# senseBox-MCU_mini_v11.net
KiCad netlist of a schematic drawn in EAGLE
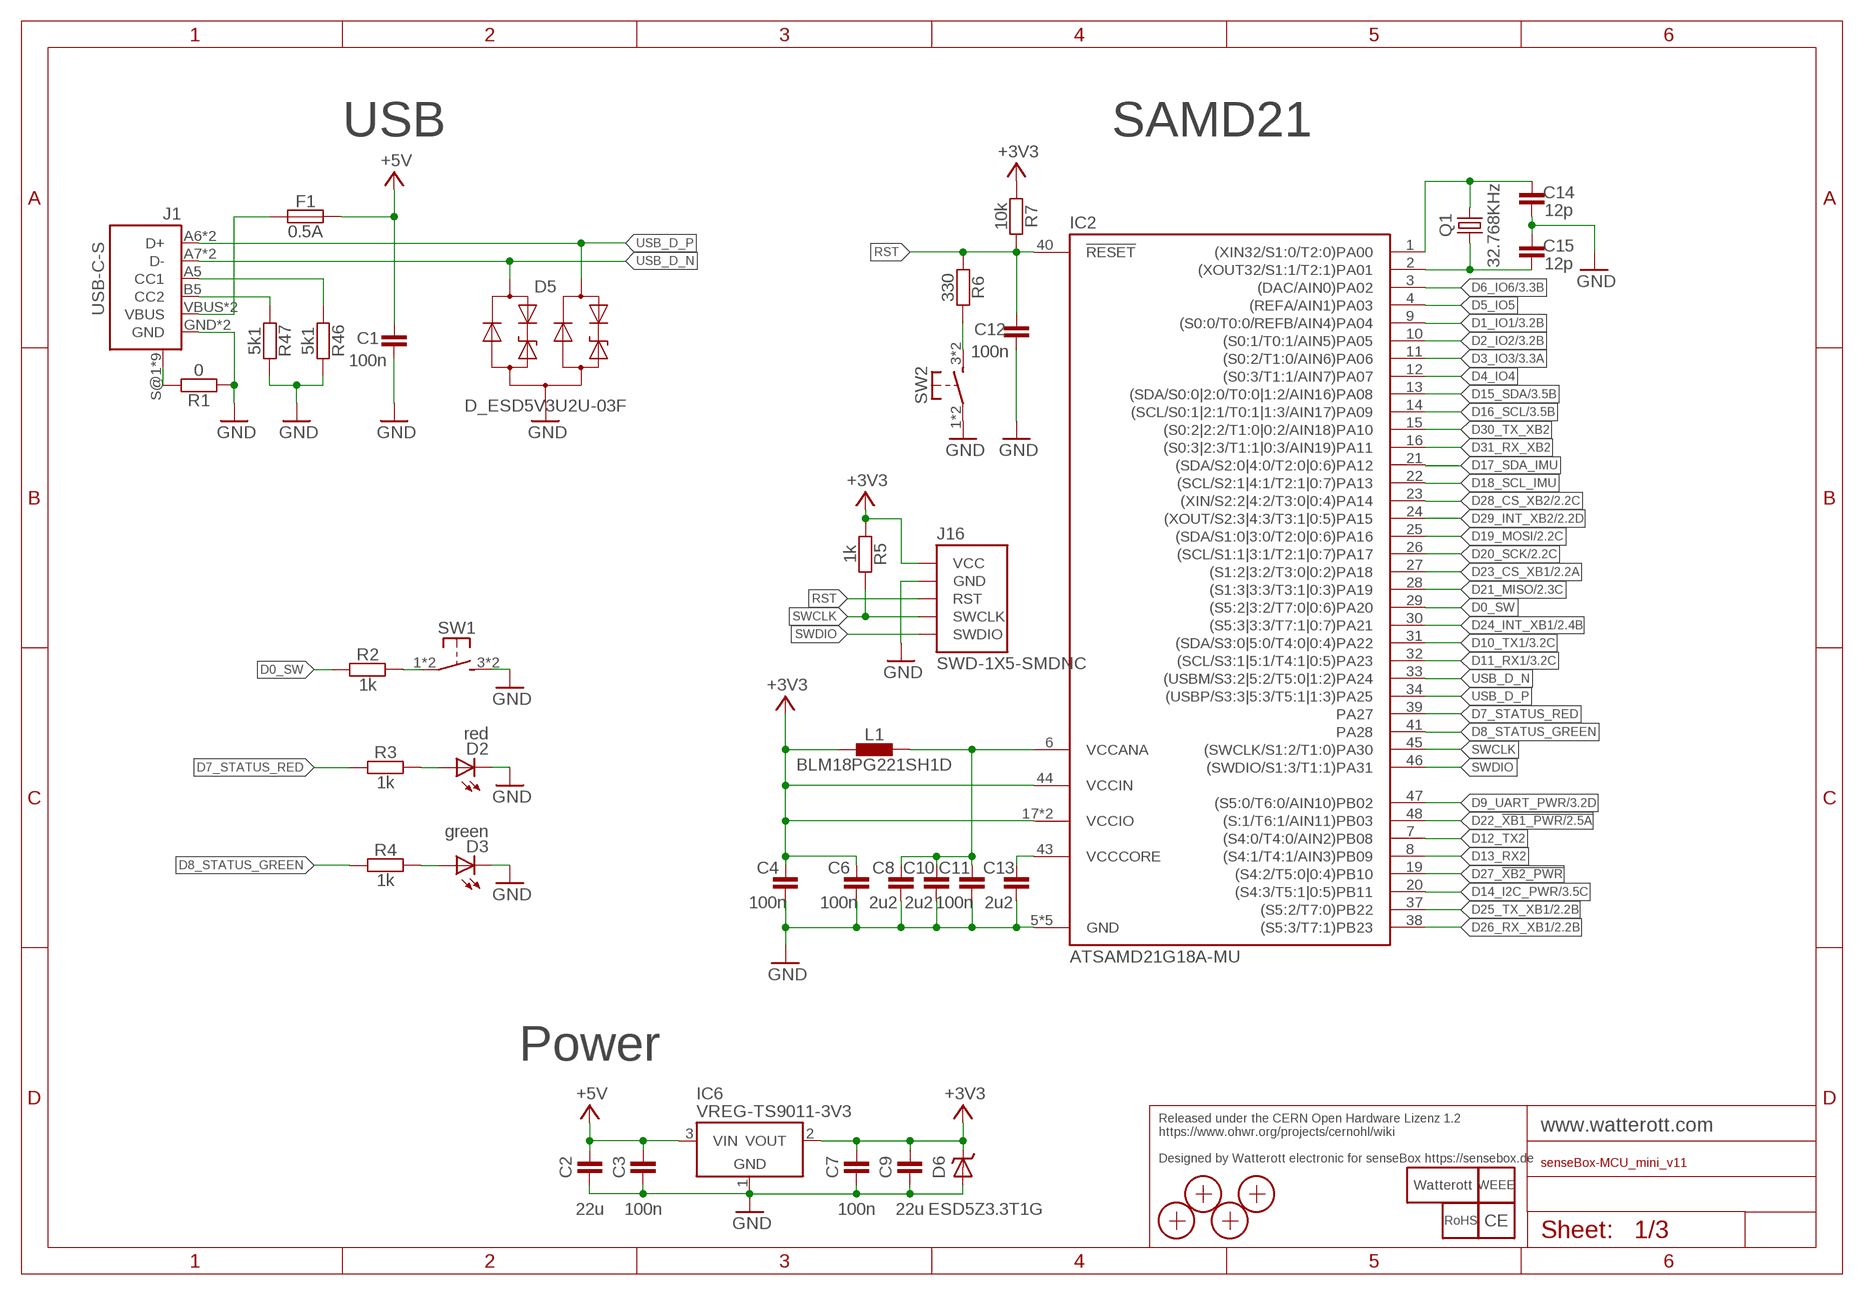
[diagram p0: schematic, sheet 1]
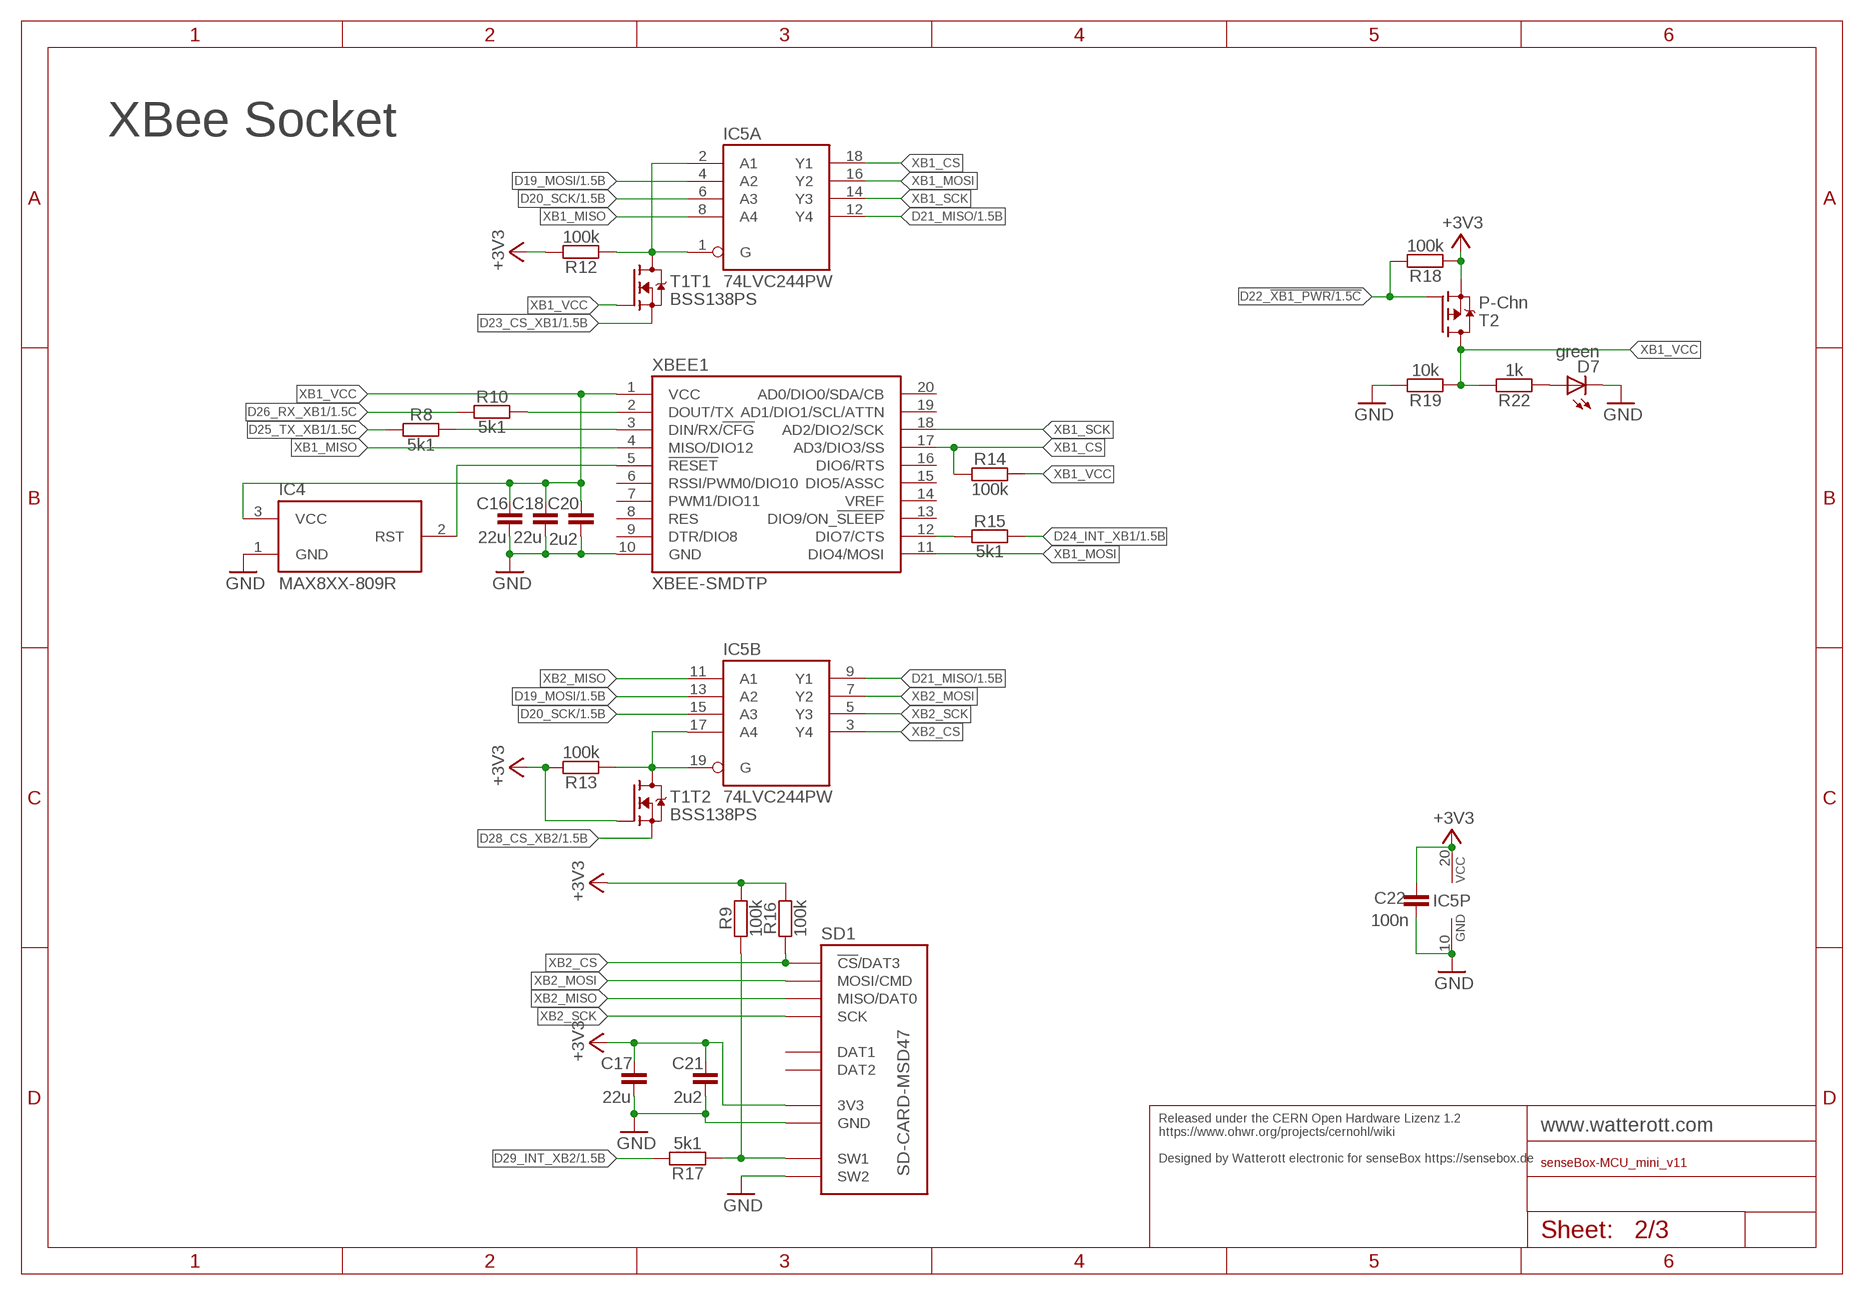
[diagram p1: schematic, sheet 2]
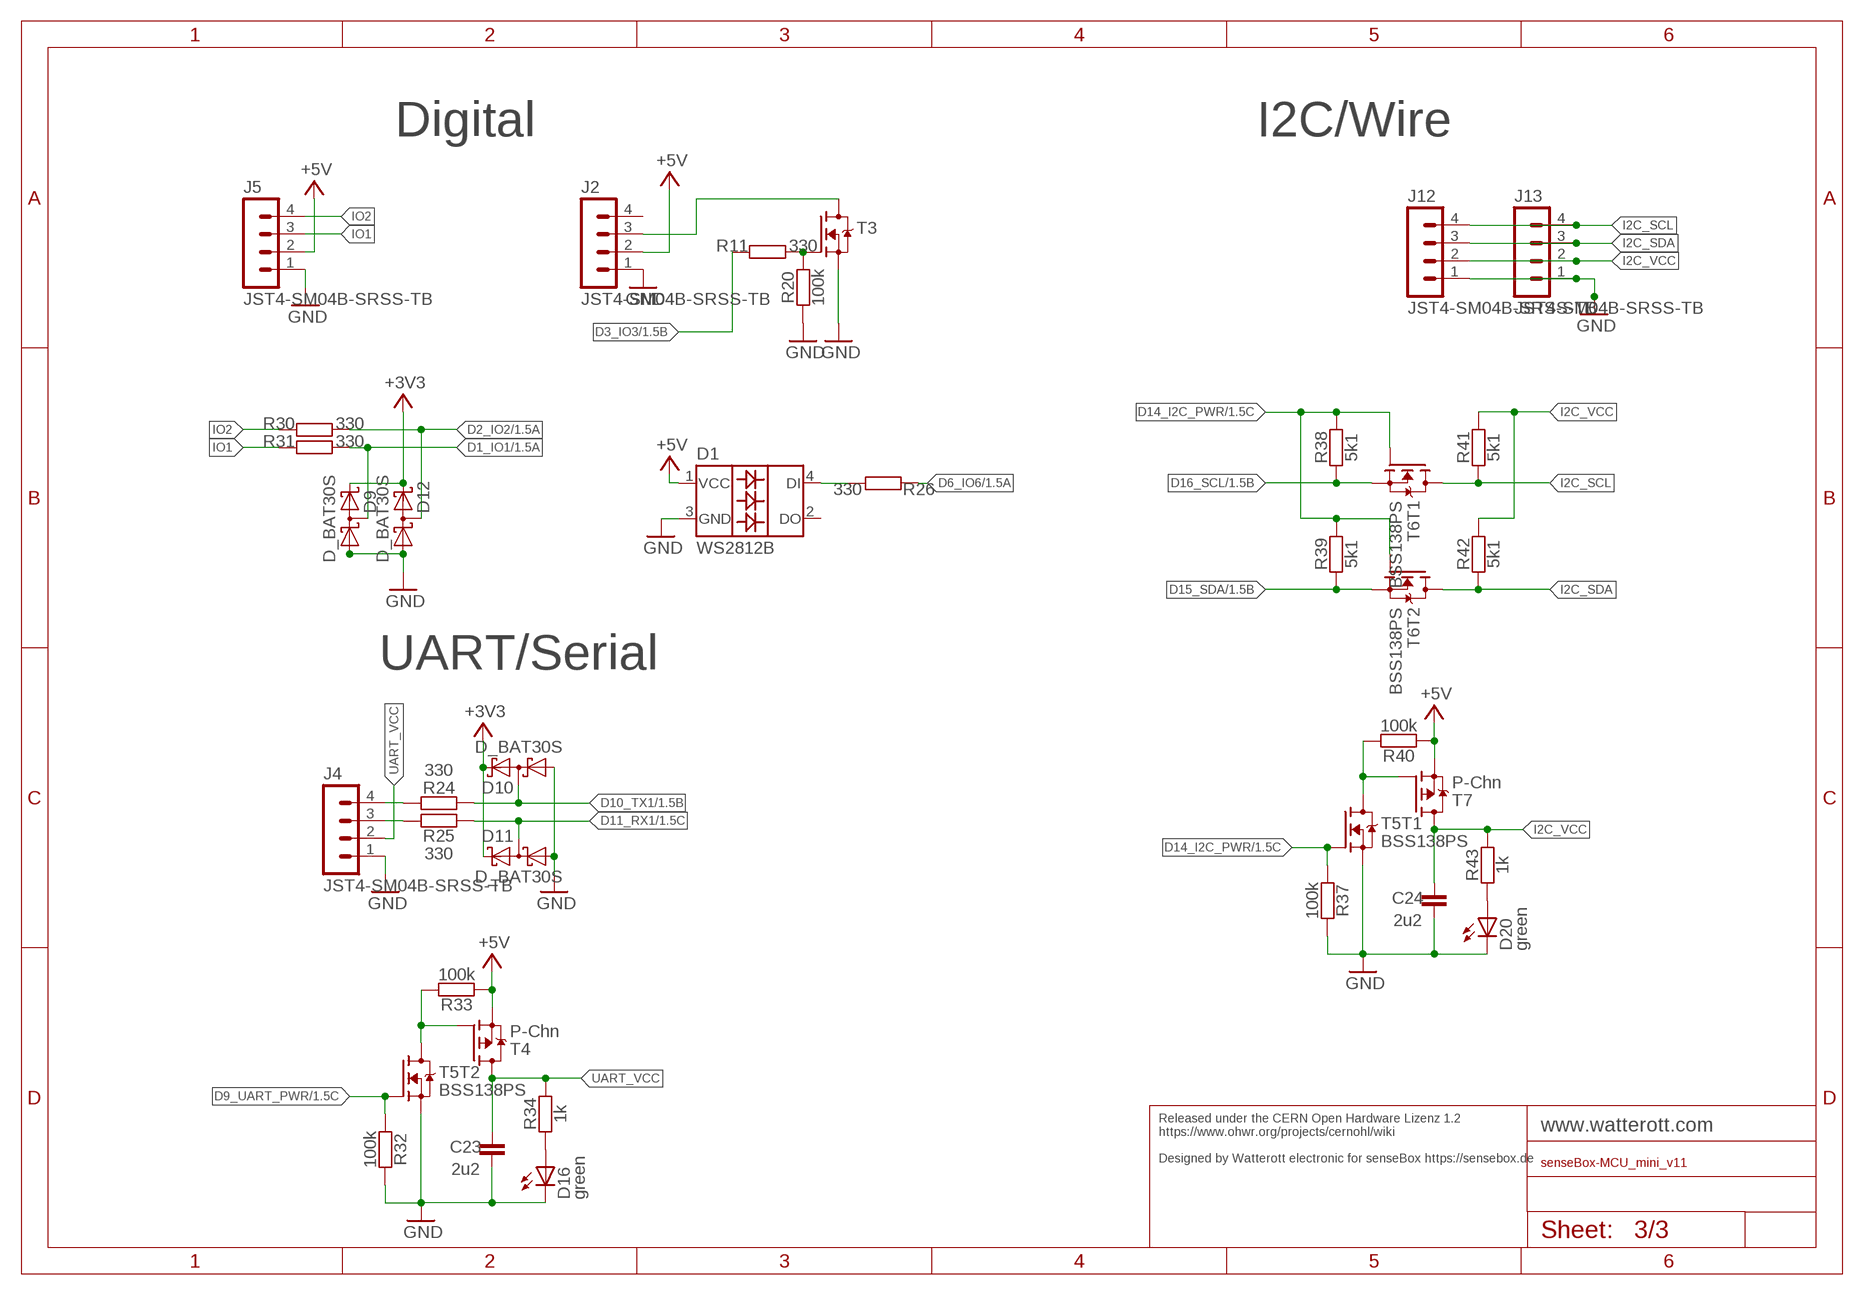
[diagram p2: schematic, sheet 3]

(export (version "E")
  (design (tool "Eeschema 10.0.6"))
  (components
    (comp (ref "C23")
      (value "2u2")
      (footprint "eagle-import:C0402")
      (libsource (lib "eagle-import") (part "CAPACITOR-0402"))
    )
    (comp (ref "C24")
      (value "2u2")
      (footprint "eagle-import:C0402")
      (libsource (lib "eagle-import") (part "CAPACITOR-0402"))
    )
    (comp (ref "D1")
      (value "WS2812B")
      (footprint "eagle-import:WS2812B")
      (libsource (lib "eagle-import") (part "WS2812B"))
    )
    (comp (ref "D9")
      (value "D_BAT30S")
      (footprint "eagle-import:SOT323")
      (libsource (lib "eagle-import") (part "D_BAT30S"))
    )
    (comp (ref "D10")
      (value "D_BAT30S")
      (footprint "eagle-import:SOT323")
      (libsource (lib "eagle-import") (part "D_BAT30S"))
    )
    (comp (ref "D11")
      (value "D_BAT30S")
      (footprint "eagle-import:SOT323")
      (libsource (lib "eagle-import") (part "D_BAT30S"))
    )
    (comp (ref "D12")
      (value "D_BAT30S")
      (footprint "eagle-import:SOT323")
      (libsource (lib "eagle-import") (part "D_BAT30S"))
    )
    (comp (ref "D16")
      (value "green")
      (footprint "eagle-import:C0603")
      (libsource (lib "eagle-import") (part "LED-0603"))
    )
    (comp (ref "D20")
      (value "green")
      (footprint "eagle-import:C0603")
      (libsource (lib "eagle-import") (part "LED-0603"))
    )
    (comp (ref "J2")
      (value "JST4-SM04B-SRSS-TB")
      (footprint "eagle-import:JST_SM04B-SRSS-TB")
      (libsource (lib "eagle-import") (part "JST4-SM04B-SRSS-TB"))
    )
    (comp (ref "J4")
      (value "JST4-SM04B-SRSS-TB")
      (footprint "eagle-import:JST_SM04B-SRSS-TB")
      (libsource (lib "eagle-import") (part "JST4-SM04B-SRSS-TB"))
    )
    (comp (ref "J5")
      (value "JST4-SM04B-SRSS-TB")
      (footprint "eagle-import:JST_SM04B-SRSS-TB")
      (libsource (lib "eagle-import") (part "JST4-SM04B-SRSS-TB"))
    )
    (comp (ref "J12")
      (value "JST4-SM04B-SRSS-TB")
      (footprint "eagle-import:JST_SM04B-SRSS-TB")
      (libsource (lib "eagle-import") (part "JST4-SM04B-SRSS-TB"))
    )
    (comp (ref "J13")
      (value "JST4-SM04B-SRSS-TB")
      (footprint "eagle-import:JST_SM04B-SRSS-TB")
      (libsource (lib "eagle-import") (part "JST4-SM04B-SRSS-TB"))
    )
    (comp (ref "R11")
      (value "330")
      (footprint "eagle-import:C0402")
      (libsource (lib "eagle-import") (part "RESISTOR-0402"))
    )
    (comp (ref "R20")
      (value "100k")
      (footprint "eagle-import:C0402")
      (libsource (lib "eagle-import") (part "RESISTOR-0402"))
    )
    (comp (ref "R24")
      (value "330")
      (footprint "eagle-import:C0402")
      (libsource (lib "eagle-import") (part "RESISTOR-0402"))
    )
    (comp (ref "R25")
      (value "330")
      (footprint "eagle-import:C0402")
      (libsource (lib "eagle-import") (part "RESISTOR-0402"))
    )
    (comp (ref "R26")
      (value "330")
      (footprint "eagle-import:C0402")
      (libsource (lib "eagle-import") (part "RESISTOR-0402"))
    )
    (comp (ref "R30")
      (value "330")
      (footprint "eagle-import:C0402")
      (libsource (lib "eagle-import") (part "RESISTOR-0402"))
    )
    (comp (ref "R31")
      (value "330")
      (footprint "eagle-import:C0402")
      (libsource (lib "eagle-import") (part "RESISTOR-0402"))
    )
    (comp (ref "R32")
      (value "100k")
      (footprint "eagle-import:C0402")
      (libsource (lib "eagle-import") (part "RESISTOR-0402"))
    )
    (comp (ref "R33")
      (value "100k")
      (footprint "eagle-import:C0402")
      (libsource (lib "eagle-import") (part "RESISTOR-0402"))
    )
    (comp (ref "R34")
      (value "1k")
      (footprint "eagle-import:C0402")
      (libsource (lib "eagle-import") (part "RESISTOR-0402"))
    )
    (comp (ref "R37")
      (value "100k")
      (footprint "eagle-import:C0402")
      (libsource (lib "eagle-import") (part "RESISTOR-0402"))
    )
    (comp (ref "R38")
      (value "5k1")
      (footprint "eagle-import:C0402")
      (libsource (lib "eagle-import") (part "RESISTOR-0402"))
    )
    (comp (ref "R39")
      (value "5k1")
      (footprint "eagle-import:C0402")
      (libsource (lib "eagle-import") (part "RESISTOR-0402"))
    )
    (comp (ref "R40")
      (value "100k")
      (footprint "eagle-import:C0402")
      (libsource (lib "eagle-import") (part "RESISTOR-0402"))
    )
    (comp (ref "R41")
      (value "5k1")
      (footprint "eagle-import:C0402")
      (libsource (lib "eagle-import") (part "RESISTOR-0402"))
    )
    (comp (ref "R42")
      (value "5k1")
      (footprint "eagle-import:C0402")
      (libsource (lib "eagle-import") (part "RESISTOR-0402"))
    )
    (comp (ref "R43")
      (value "1k")
      (footprint "eagle-import:C0402")
      (libsource (lib "eagle-import") (part "RESISTOR-0402"))
    )
    (comp (ref "T3")
      (value "MOSFET-N-SOT23")
      (footprint "eagle-import:SOT23")
      (libsource (lib "eagle-import") (part "MOSFET-N-SOT23"))
    )
    (comp (ref "T4")
      (value "P-Chn")
      (footprint "eagle-import:SOT23")
      (libsource (lib "eagle-import") (part "MOSFET-P-SOT23"))
    )
    (comp (ref "T5")
      (value "BSS138PS")
      (footprint "eagle-import:SOT363")
      (libsource (lib "eagle-import") (part "BSS138PS"))
    )
    (comp (ref "T6")
      (value "BSS138PS")
      (footprint "eagle-import:SOT363")
      (libsource (lib "eagle-import") (part "BSS138PS"))
    )
    (comp (ref "T7")
      (value "P-Chn")
      (footprint "eagle-import:SOT23")
      (libsource (lib "eagle-import") (part "MOSFET-P-SOT23"))
    )
    (comp (ref "C16")
      (value "22u")
      (footprint "eagle-import:C0805")
      (libsource (lib "eagle-import") (part "CAPACITOR-0805"))
    )
    (comp (ref "C17")
      (value "22u")
      (footprint "eagle-import:C0805")
      (libsource (lib "eagle-import") (part "CAPACITOR-0805"))
    )
    (comp (ref "C18")
      (value "22u")
      (footprint "eagle-import:C0805")
      (libsource (lib "eagle-import") (part "CAPACITOR-0805"))
    )
    (comp (ref "C20")
      (value "2u2")
      (footprint "eagle-import:C0402")
      (libsource (lib "eagle-import") (part "CAPACITOR-0402"))
    )
    (comp (ref "C21")
      (value "2u2")
      (footprint "eagle-import:C0402")
      (libsource (lib "eagle-import") (part "CAPACITOR-0402"))
    )
    (comp (ref "C22")
      (value "100n")
      (footprint "eagle-import:C0402")
      (libsource (lib "eagle-import") (part "CAPACITOR-0402"))
    )
    (comp (ref "D7")
      (value "green")
      (footprint "eagle-import:C0603")
      (libsource (lib "eagle-import") (part "LED-0603"))
    )
    (comp (ref "IC4")
      (value "MAX8XX-809R")
      (footprint "eagle-import:SOT23")
      (libsource (lib "eagle-import") (part "MAX8XX-809R"))
    )
    (comp (ref "IC5")
      (value "74LVC244PW")
      (footprint "eagle-import:TSSOP20")
      (libsource (lib "eagle-import") (part "74244PWLVC"))
    )
    (comp (ref "R8")
      (value "5k1")
      (footprint "eagle-import:C0402")
      (libsource (lib "eagle-import") (part "RESISTOR-0402"))
    )
    (comp (ref "R9")
      (value "100k")
      (footprint "eagle-import:C0402")
      (libsource (lib "eagle-import") (part "RESISTOR-0402"))
    )
    (comp (ref "R10")
      (value "5k1")
      (footprint "eagle-import:C0402")
      (libsource (lib "eagle-import") (part "RESISTOR-0402"))
    )
    (comp (ref "R12")
      (value "100k")
      (footprint "eagle-import:C0402")
      (libsource (lib "eagle-import") (part "RESISTOR-0402"))
    )
    (comp (ref "R13")
      (value "100k")
      (footprint "eagle-import:C0402")
      (libsource (lib "eagle-import") (part "RESISTOR-0402"))
    )
    (comp (ref "R14")
      (value "100k")
      (footprint "eagle-import:C0402")
      (libsource (lib "eagle-import") (part "RESISTOR-0402"))
    )
    (comp (ref "R15")
      (value "5k1")
      (footprint "eagle-import:C0402")
      (libsource (lib "eagle-import") (part "RESISTOR-0402"))
    )
    (comp (ref "R16")
      (value "100k")
      (footprint "eagle-import:C0402")
      (libsource (lib "eagle-import") (part "RESISTOR-0402"))
    )
    (comp (ref "R17")
      (value "5k1")
      (footprint "eagle-import:C0402")
      (libsource (lib "eagle-import") (part "RESISTOR-0402"))
    )
    (comp (ref "R18")
      (value "100k")
      (footprint "eagle-import:C0402")
      (libsource (lib "eagle-import") (part "RESISTOR-0402"))
    )
    (comp (ref "R19")
      (value "10k")
      (footprint "eagle-import:C0402")
      (libsource (lib "eagle-import") (part "RESISTOR-0402"))
    )
    (comp (ref "R22")
      (value "1k")
      (footprint "eagle-import:C0402")
      (libsource (lib "eagle-import") (part "RESISTOR-0402"))
    )
    (comp (ref "SD1")
      (value "SD-CARD-MSD47")
      (footprint "eagle-import:SD_47309XXXX")
      (libsource (lib "eagle-import") (part "SD-CARD-MSD47"))
    )
    (comp (ref "T1")
      (value "BSS138PS")
      (footprint "eagle-import:SOT363")
      (libsource (lib "eagle-import") (part "BSS138PS"))
    )
    (comp (ref "T2")
      (value "P-Chn")
      (footprint "eagle-import:SOT23")
      (libsource (lib "eagle-import") (part "MOSFET-P-SOT23"))
    )
    (comp (ref "XBEE1")
      (value "XBEE-SMDTP")
      (footprint "eagle-import:XBEE_SMD_TP")
      (libsource (lib "eagle-import") (part "XBEE-SMDTP"))
    )
    (comp (ref "C1")
      (value "100n")
      (footprint "eagle-import:C0402")
      (libsource (lib "eagle-import") (part "CAPACITOR-0402"))
    )
    (comp (ref "C2")
      (value "22u")
      (footprint "eagle-import:C0805")
      (libsource (lib "eagle-import") (part "CAPACITOR-0805"))
    )
    (comp (ref "C3")
      (value "100n")
      (footprint "eagle-import:C0402")
      (libsource (lib "eagle-import") (part "CAPACITOR-0402"))
    )
    (comp (ref "C4")
      (value "100n")
      (footprint "eagle-import:C0402")
      (libsource (lib "eagle-import") (part "CAPACITOR-0402"))
    )
    (comp (ref "C6")
      (value "100n")
      (footprint "eagle-import:C0402")
      (libsource (lib "eagle-import") (part "CAPACITOR-0402"))
    )
    (comp (ref "C7")
      (value "100n")
      (footprint "eagle-import:C0402")
      (libsource (lib "eagle-import") (part "CAPACITOR-0402"))
    )
    (comp (ref "C8")
      (value "2u2")
      (footprint "eagle-import:C0402")
      (libsource (lib "eagle-import") (part "CAPACITOR-0402"))
    )
    (comp (ref "C9")
      (value "22u")
      (footprint "eagle-import:C0805")
      (libsource (lib "eagle-import") (part "CAPACITOR-0805"))
    )
    (comp (ref "C10")
      (value "2u2")
      (footprint "eagle-import:C0402")
      (libsource (lib "eagle-import") (part "CAPACITOR-0402"))
    )
    (comp (ref "C11")
      (value "100n")
      (footprint "eagle-import:C0402")
      (libsource (lib "eagle-import") (part "CAPACITOR-0402"))
    )
    (comp (ref "C12")
      (value "100n")
      (footprint "eagle-import:C0402")
      (libsource (lib "eagle-import") (part "CAPACITOR-0402"))
    )
    (comp (ref "C13")
      (value "2u2")
      (footprint "eagle-import:C0402")
      (libsource (lib "eagle-import") (part "CAPACITOR-0402"))
    )
    (comp (ref "C14")
      (value "12p")
      (footprint "eagle-import:C0402")
      (libsource (lib "eagle-import") (part "CAPACITOR-0402"))
    )
    (comp (ref "C15")
      (value "12p")
      (footprint "eagle-import:C0402")
      (libsource (lib "eagle-import") (part "CAPACITOR-0402"))
    )
    (comp (ref "D2")
      (value "red")
      (footprint "eagle-import:C0603")
      (libsource (lib "eagle-import") (part "LED-0603"))
    )
    (comp (ref "D3")
      (value "green")
      (footprint "eagle-import:C0603")
      (libsource (lib "eagle-import") (part "LED-0603"))
    )
    (comp (ref "D5")
      (value "D_ESD5V3U2U-03F")
      (footprint "eagle-import:SOT723")
      (libsource (lib "eagle-import") (part "D_ESD5V3U2U-03F"))
    )
    (comp (ref "D6")
      (value "ESD5Z3.3T1G")
      (footprint "eagle-import:SOD523")
      (libsource (lib "eagle-import") (part "D_TVS-SOD523"))
    )
    (comp (ref "F1")
      (value "0.5A")
      (footprint "eagle-import:C0805")
      (libsource (lib "eagle-import") (part "FUSE-0805"))
    )
    (comp (ref "IC2")
      (value "ATSAMD21G18A-MU")
      (footprint "eagle-import:QFN48-PAD")
      (libsource (lib "eagle-import") (part "ATSAMD21G18A-MU"))
    )
    (comp (ref "IC6")
      (value "VREG-TS9011-3V3")
      (footprint "eagle-import:SOT23")
      (libsource (lib "eagle-import") (part "VREG-TS9011-3V3"))
    )
    (comp (ref "J1")
      (value "USB-C-S")
      (footprint "eagle-import:USB-C-S")
      (libsource (lib "eagle-import") (part "USB-C-S"))
    )
    (comp (ref "J16")
      (value "SWD-1X5-SMDNC")
      (footprint "eagle-import:SWD-1X5_SMDNC")
      (libsource (lib "eagle-import") (part "SWD-1X5-SMDNC"))
    )
    (comp (ref "L1")
      (value "BLM18PG221SH1D")
      (footprint "eagle-import:C0603")
      (libsource (lib "eagle-import") (part "INDUCTOR-0603"))
    )
    (comp (ref "LOGO4")
      (value "LOGO_SPARK-4")
      (footprint "eagle-import:SPARK_4MM")
      (libsource (lib "eagle-import") (part "LOGO_SPARK-4"))
    )
    (comp (ref "LOGO5")
      (value "LOGO_ROHS-2")
      (footprint "eagle-import:ROHS_2MM")
      (libsource (lib "eagle-import") (part "LOGO_ROHS-2"))
    )
    (comp (ref "LOGO6")
      (value "LOGO_WEEE-4")
      (footprint "eagle-import:WEEE_4MM")
      (libsource (lib "eagle-import") (part "LOGO_WEEE-4"))
    )
    (comp (ref "LOGO7")
      (value "LOGO_CE-2")
      (footprint "eagle-import:CE_2MM")
      (libsource (lib "eagle-import") (part "LOGO_CE-2"))
    )
    (comp (ref "Q1")
      (value "32.768KHz")
      (footprint "eagle-import:CRYSTAL_ZM315")
      (libsource (lib "eagle-import") (part "CRYSTAL-ZM315"))
    )
    (comp (ref "R1")
      (value "0")
      (footprint "eagle-import:C0402")
      (libsource (lib "eagle-import") (part "RESISTOR-0402"))
    )
    (comp (ref "R2")
      (value "1k")
      (footprint "eagle-import:C0402")
      (libsource (lib "eagle-import") (part "RESISTOR-0402"))
    )
    (comp (ref "R3")
      (value "1k")
      (footprint "eagle-import:C0402")
      (libsource (lib "eagle-import") (part "RESISTOR-0402"))
    )
    (comp (ref "R4")
      (value "1k")
      (footprint "eagle-import:C0402")
      (libsource (lib "eagle-import") (part "RESISTOR-0402"))
    )
    (comp (ref "R5")
      (value "1k")
      (footprint "eagle-import:C0402")
      (libsource (lib "eagle-import") (part "RESISTOR-0402"))
    )
    (comp (ref "R6")
      (value "330")
      (footprint "eagle-import:C0402")
      (libsource (lib "eagle-import") (part "RESISTOR-0402"))
    )
    (comp (ref "R7")
      (value "10k")
      (footprint "eagle-import:C0402")
      (libsource (lib "eagle-import") (part "RESISTOR-0402"))
    )
    (comp (ref "R46")
      (value "5k1")
      (footprint "eagle-import:C0402")
      (libsource (lib "eagle-import") (part "RESISTOR-0402"))
    )
    (comp (ref "R47")
      (value "5k1")
      (footprint "eagle-import:C0402")
      (libsource (lib "eagle-import") (part "RESISTOR-0402"))
    )
    (comp (ref "SW1")
      (value "PTS645SH50SMTR92-Grey")
      (footprint "eagle-import:PTS840P")
      (libsource (lib "eagle-import") (part "SW-TACTILE-PTS840P"))
    )
    (comp (ref "SW2")
      (value "PTS645SK50SMTR92-Red")
      (footprint "eagle-import:PTS840P")
      (libsource (lib "eagle-import") (part "SW-TACTILE-PTS840P"))
    )
    (comp (ref "X1")
      (value "PASSER-07")
      (footprint "eagle-import:PASSER_07MM")
      (libsource (lib "eagle-import") (part "PASSER-07"))
    )
    (comp (ref "X2")
      (value "PASSER-07")
      (footprint "eagle-import:PASSER_07MM")
      (libsource (lib "eagle-import") (part "PASSER-07"))
    )
    (comp (ref "X3")
      (value "PASSER-07")
      (footprint "eagle-import:PASSER_07MM")
      (libsource (lib "eagle-import") (part "PASSER-07"))
    )
    (comp (ref "X4")
      (value "PASSER-07")
      (footprint "eagle-import:PASSER_07MM")
      (libsource (lib "eagle-import") (part "PASSER-07"))
    )
  )
  (nets
    (net (code "1") (name "+3V3") (class "Default")
      (node (ref "C17") (pin "2") (pinfunction "2_2") (pintype "passive"))
      (node (ref "C21") (pin "2") (pinfunction "2_2") (pintype "passive"))
      (node (ref "C22") (pin "2") (pinfunction "2_2") (pintype "passive"))
      (node (ref "C4") (pin "2") (pinfunction "2_2") (pintype "passive"))
      (node (ref "C6") (pin "2") (pinfunction "2_2") (pintype "passive"))
      (node (ref "C7") (pin "2") (pinfunction "2_2") (pintype "passive"))
      (node (ref "C9") (pin "2") (pinfunction "2_2") (pintype "passive"))
      (node (ref "D10") (pin "2") (pinfunction "C_2") (pintype "passive"))
      (node (ref "D11") (pin "2") (pinfunction "C_2") (pintype "passive"))
      (node (ref "D12") (pin "2") (pinfunction "C_2") (pintype "passive"))
      (node (ref "D6") (pin "C") (pinfunction "C_C") (pintype "passive"))
      (node (ref "D9") (pin "2") (pinfunction "C_2") (pintype "passive"))
      (node (ref "IC2") (pin "17") (pinfunction "VCCIO_17") (pintype "power_in"))
      (node (ref "IC2") (pin "36") (pinfunction "VCCIO_36") (pintype "power_in"))
      (node (ref "IC2") (pin "44") (pinfunction "VCCIN_44") (pintype "power_in"))
      (node (ref "IC5") (pin "20") (pinfunction "VCC_20") (pintype "power_in"))
      (node (ref "IC6") (pin "2") (pinfunction "VOUT_2") (pintype "power_in"))
      (node (ref "J16") (pin "1-VCC") (pinfunction "VCC_1-VCC") (pintype "power_in"))
      (node (ref "L1") (pin "1") (pinfunction "1_1") (pintype "passive"))
      (node (ref "R12") (pin "2") (pinfunction "2_2") (pintype "passive"))
      (node (ref "R13") (pin "2") (pinfunction "2_2") (pintype "passive"))
      (node (ref "R16") (pin "2") (pinfunction "2_2") (pintype "passive"))
      (node (ref "R18") (pin "1") (pinfunction "1_1") (pintype "passive"))
      (node (ref "R5") (pin "1") (pinfunction "1_1") (pintype "passive"))
      (node (ref "R7") (pin "1") (pinfunction "1_1") (pintype "passive"))
      (node (ref "R9") (pin "2") (pinfunction "2_2") (pintype "passive"))
      (node (ref "SD1") (pin "VCC") (pinfunction "3V3_VCC") (pintype "bidirectional"))
      (node (ref "T1") (pin "5") (pinfunction "G_5") (pintype "passive"))
      (node (ref "T2") (pin "2") (pinfunction "S_2") (pintype "passive"))
    )
    (net (code "2") (name "+5V") (class "Default")
      (node (ref "C1") (pin "2") (pinfunction "2_2") (pintype "passive"))
      (node (ref "C2") (pin "2") (pinfunction "2_2") (pintype "passive"))
      (node (ref "C3") (pin "2") (pinfunction "2_2") (pintype "passive"))
      (node (ref "D1") (pin "1") (pinfunction "VCC_1") (pintype "power_in"))
      (node (ref "F1") (pin "2") (pinfunction "2_2") (pintype "passive"))
      (node (ref "IC6") (pin "3") (pinfunction "VIN_3") (pintype "power_in"))
      (node (ref "J2") (pin "2") (pinfunction "2_2") (pintype "passive"))
      (node (ref "J5") (pin "2") (pinfunction "2_2") (pintype "passive"))
      (node (ref "R33") (pin "1") (pinfunction "1_1") (pintype "passive"))
      (node (ref "R40") (pin "1") (pinfunction "1_1") (pintype "passive"))
      (node (ref "T4") (pin "2") (pinfunction "S_2") (pintype "passive"))
      (node (ref "T7") (pin "2") (pinfunction "S_2") (pintype "passive"))
    )
    (net (code "3") (name "D0_SW") (class "Default")
      (node (ref "IC2") (pin "29") (pinfunction "(S5:2|3:2/T7:0|0:6)PA20_29") (pintype "bidirectional"))
      (node (ref "R2") (pin "1") (pinfunction "1_1") (pintype "passive"))
    )
    (net (code "4") (name "D1_IO1") (class "Default")
      (node (ref "D9") (pin "3") (pinfunction "CA_3") (pintype "passive"))
      (node (ref "IC2") (pin "9") (pinfunction "(S0:0/T0:0/REFB/AIN4)PA04_9") (pintype "bidirectional"))
      (node (ref "R31") (pin "1") (pinfunction "1_1") (pintype "passive"))
    )
    (net (code "5") (name "D2_IO2") (class "Default")
      (node (ref "D12") (pin "3") (pinfunction "CA_3") (pintype "passive"))
      (node (ref "IC2") (pin "10") (pinfunction "(S0:1/T0:1/AIN5)PA05_10") (pintype "bidirectional"))
      (node (ref "R30") (pin "1") (pinfunction "1_1") (pintype "passive"))
    )
    (net (code "6") (name "D3_IO3") (class "Default")
      (node (ref "IC2") (pin "11") (pinfunction "(S0:2/T1:0/AIN6)PA06_11") (pintype "bidirectional"))
      (node (ref "R11") (pin "2") (pinfunction "2_2") (pintype "passive"))
    )
    (net (code "7") (name "D4_IO4") (class "Default")
      (node (ref "IC2") (pin "12") (pinfunction "(S0:3/T1:1/AIN7)PA07_12") (pintype "bidirectional"))
    )
    (net (code "8") (name "D5_IO5") (class "Default")
      (node (ref "IC2") (pin "4") (pinfunction "(REFA/AIN1)PA03_4") (pintype "bidirectional"))
    )
    (net (code "9") (name "D6_IO6") (class "Default")
      (node (ref "IC2") (pin "3") (pinfunction "(DAC/AIN0)PA02_3") (pintype "bidirectional"))
      (node (ref "R26") (pin "2") (pinfunction "2_2") (pintype "passive"))
    )
    (net (code "10") (name "D7_STATUS_RED") (class "Default")
      (node (ref "IC2") (pin "39") (pinfunction "PA27_39") (pintype "bidirectional"))
      (node (ref "R3") (pin "1") (pinfunction "1_1") (pintype "passive"))
    )
    (net (code "11") (name "D8_STATUS_GREEN") (class "Default")
      (node (ref "IC2") (pin "41") (pinfunction "PA28_41") (pintype "bidirectional"))
      (node (ref "R4") (pin "1") (pinfunction "1_1") (pintype "passive"))
    )
    (net (code "12") (name "D9_UART_PWR") (class "Default")
      (node (ref "IC2") (pin "47") (pinfunction "(S5:0/T6:0/AIN10)PB02_47") (pintype "bidirectional"))
      (node (ref "R32") (pin "1") (pinfunction "1_1") (pintype "passive"))
      (node (ref "T5") (pin "5") (pinfunction "G_5") (pintype "passive"))
    )
    (net (code "13") (name "D10_TX1") (class "Default")
      (node (ref "D10") (pin "3") (pinfunction "CA_3") (pintype "passive"))
      (node (ref "IC2") (pin "31") (pinfunction "(SDA/S3:0|5:0/T4:0|0:4)PA22_31") (pintype "bidirectional"))
      (node (ref "R24") (pin "1") (pinfunction "1_1") (pintype "passive"))
    )
    (net (code "14") (name "D11_RX1") (class "Default")
      (node (ref "D11") (pin "3") (pinfunction "CA_3") (pintype "passive"))
      (node (ref "IC2") (pin "32") (pinfunction "(SCL/S3:1|5:1/T4:1|0:5)PA23_32") (pintype "bidirectional"))
      (node (ref "R25") (pin "1") (pinfunction "1_1") (pintype "passive"))
    )
    (net (code "15") (name "D12_TX2") (class "Default")
      (node (ref "IC2") (pin "7") (pinfunction "(S4:0/T4:0/AIN2)PB08_7") (pintype "bidirectional"))
    )
    (net (code "16") (name "D13_RX2") (class "Default")
      (node (ref "IC2") (pin "8") (pinfunction "(S4:1/T4:1/AIN3)PB09_8") (pintype "bidirectional"))
    )
    (net (code "17") (name "D14_I2C_PWR") (class "Default")
      (node (ref "IC2") (pin "20") (pinfunction "(S4:3/T5:1|0:5)PB11_20") (pintype "bidirectional"))
      (node (ref "R37") (pin "1") (pinfunction "1_1") (pintype "passive"))
      (node (ref "R38") (pin "2") (pinfunction "2_2") (pintype "passive"))
      (node (ref "R39") (pin "2") (pinfunction "2_2") (pintype "passive"))
      (node (ref "T5") (pin "2") (pinfunction "G_2") (pintype "passive"))
      (node (ref "T6") (pin "2") (pinfunction "G_2") (pintype "passive"))
      (node (ref "T6") (pin "5") (pinfunction "G_5") (pintype "passive"))
    )
    (net (code "18") (name "D15_SDA") (class "Default")
      (node (ref "IC2") (pin "13") (pinfunction "(SDA/S0:0|2:0/T0:0|1:2/AIN16)PA08_13") (pintype "bidirectional"))
      (node (ref "R39") (pin "1") (pinfunction "1_1") (pintype "passive"))
      (node (ref "T6") (pin "4") (pinfunction "S_4") (pintype "passive"))
    )
    (net (code "19") (name "D16_SCL") (class "Default")
      (node (ref "IC2") (pin "14") (pinfunction "(SCL/S0:1|2:1/T0:1|1:3/AIN17)PA09_14") (pintype "bidirectional"))
      (node (ref "R38") (pin "1") (pinfunction "1_1") (pintype "passive"))
      (node (ref "T6") (pin "1") (pinfunction "S_1") (pintype "passive"))
    )
    (net (code "20") (name "D17_SDA_IMU") (class "Default")
      (node (ref "IC2") (pin "21") (pinfunction "(SDA/S2:0|4:0/T2:0|0:6)PA12_21") (pintype "bidirectional"))
    )
    (net (code "21") (name "D18_SCL_IMU") (class "Default")
      (node (ref "IC2") (pin "22") (pinfunction "(SCL/S2:1|4:1/T2:1|0:7)PA13_22") (pintype "bidirectional"))
    )
    (net (code "22") (name "D19_MOSI") (class "Default")
      (node (ref "IC2") (pin "25") (pinfunction "(SDA/S1:0|3:0/T2:0|0:6)PA16_25") (pintype "bidirectional"))
      (node (ref "IC5") (pin "13") (pinfunction "A2_13") (pintype "input"))
      (node (ref "IC5") (pin "4") (pinfunction "A2_4") (pintype "input"))
    )
    (net (code "23") (name "D20_SCK") (class "Default")
      (node (ref "IC2") (pin "26") (pinfunction "(SCL/S1:1|3:1/T2:1|0:7)PA17_26") (pintype "bidirectional"))
      (node (ref "IC5") (pin "15") (pinfunction "A3_15") (pintype "input"))
      (node (ref "IC5") (pin "6") (pinfunction "A3_6") (pintype "input"))
    )
    (net (code "24") (name "D21_MISO") (class "Default")
      (node (ref "IC2") (pin "28") (pinfunction "(S1:3|3:3/T3:1|0:3)PA19_28") (pintype "bidirectional"))
      (node (ref "IC5") (pin "12") (pinfunction "Y4_12") (pintype "tri_state"))
      (node (ref "IC5") (pin "9") (pinfunction "Y1_9") (pintype "tri_state"))
    )
    (net (code "25") (name "D22_~{XB1_PWR}") (class "Default")
      (node (ref "IC2") (pin "48") (pinfunction "(S:1/T6:1/AIN11)PB03_48") (pintype "bidirectional"))
      (node (ref "R18") (pin "2") (pinfunction "2_2") (pintype "passive"))
      (node (ref "T2") (pin "1") (pinfunction "G_1") (pintype "passive"))
    )
    (net (code "26") (name "D23_CS_XB1") (class "Default")
      (node (ref "IC2") (pin "27") (pinfunction "(S1:2|3:2/T3:0|0:2)PA18_27") (pintype "bidirectional"))
      (node (ref "T1") (pin "1") (pinfunction "S_1") (pintype "passive"))
    )
    (net (code "27") (name "D24_INT_XB1") (class "Default")
      (node (ref "IC2") (pin "30") (pinfunction "(S5:3|3:3/T7:1|0:7)PA21_30") (pintype "bidirectional"))
      (node (ref "R15") (pin "2") (pinfunction "2_2") (pintype "passive"))
    )
    (net (code "28") (name "D25_TX_XB1") (class "Default")
      (node (ref "IC2") (pin "37") (pinfunction "(S5:2/T7:0)PB22_37") (pintype "bidirectional"))
      (node (ref "R8") (pin "1") (pinfunction "1_1") (pintype "passive"))
    )
    (net (code "29") (name "D26_RX_XB1") (class "Default")
      (node (ref "IC2") (pin "38") (pinfunction "(S5:3/T7:1)PB23_38") (pintype "bidirectional"))
      (node (ref "R10") (pin "1") (pinfunction "1_1") (pintype "passive"))
    )
    (net (code "30") (name "D27_~{XB2_PWR}") (class "Default")
      (node (ref "IC2") (pin "19") (pinfunction "(S4:2/T5:0|0:4)PB10_19") (pintype "bidirectional"))
    )
    (net (code "31") (name "D28_CS_XB2") (class "Default")
      (node (ref "IC2") (pin "23") (pinfunction "(XIN/S2:2|4:2/T3:0|0:4)PA14_23") (pintype "bidirectional"))
      (node (ref "T1") (pin "4") (pinfunction "S_4") (pintype "passive"))
    )
    (net (code "32") (name "D29_INT_XB2") (class "Default")
      (node (ref "IC2") (pin "24") (pinfunction "(XOUT/S2:3|4:3/T3:1|0:5)PA15_24") (pintype "bidirectional"))
      (node (ref "R17") (pin "2") (pinfunction "2_2") (pintype "passive"))
    )
    (net (code "33") (name "D30_TX_XB2") (class "Default")
      (node (ref "IC2") (pin "15") (pinfunction "(S0:2|2:2/T1:0|0:2/AIN18)PA10_15") (pintype "bidirectional"))
    )
    (net (code "34") (name "D31_RX_XB2") (class "Default")
      (node (ref "IC2") (pin "16") (pinfunction "(S0:3|2:3/T1:1|0:3/AIN19)PA11_16") (pintype "bidirectional"))
    )
    (net (code "35") (name "GND") (class "Default")
      (node (ref "C1") (pin "1") (pinfunction "1_1") (pintype "passive"))
      (node (ref "C10") (pin "1") (pinfunction "1_1") (pintype "passive"))
      (node (ref "C11") (pin "1") (pinfunction "1_1") (pintype "passive"))
      (node (ref "C12") (pin "1") (pinfunction "1_1") (pintype "passive"))
      (node (ref "C13") (pin "1") (pinfunction "1_1") (pintype "passive"))
      (node (ref "C14") (pin "2") (pinfunction "2_2") (pintype "passive"))
      (node (ref "C15") (pin "1") (pinfunction "1_1") (pintype "passive"))
      (node (ref "C16") (pin "1") (pinfunction "1_1") (pintype "passive"))
      (node (ref "C17") (pin "1") (pinfunction "1_1") (pintype "passive"))
      (node (ref "C18") (pin "1") (pinfunction "1_1") (pintype "passive"))
      (node (ref "C2") (pin "1") (pinfunction "1_1") (pintype "passive"))
      (node (ref "C20") (pin "1") (pinfunction "1_1") (pintype "passive"))
      (node (ref "C21") (pin "1") (pinfunction "1_1") (pintype "passive"))
      (node (ref "C22") (pin "1") (pinfunction "1_1") (pintype "passive"))
      (node (ref "C23") (pin "1") (pinfunction "1_1") (pintype "passive"))
      (node (ref "C24") (pin "1") (pinfunction "1_1") (pintype "passive"))
      (node (ref "C3") (pin "1") (pinfunction "1_1") (pintype "passive"))
      (node (ref "C4") (pin "1") (pinfunction "1_1") (pintype "passive"))
      (node (ref "C6") (pin "1") (pinfunction "1_1") (pintype "passive"))
      (node (ref "C7") (pin "1") (pinfunction "1_1") (pintype "passive"))
      (node (ref "C8") (pin "1") (pinfunction "1_1") (pintype "passive"))
      (node (ref "C9") (pin "1") (pinfunction "1_1") (pintype "passive"))
      (node (ref "D1") (pin "3") (pinfunction "GND_3") (pintype "power_in"))
      (node (ref "D10") (pin "1") (pinfunction "A_1") (pintype "passive"))
      (node (ref "D11") (pin "1") (pinfunction "A_1") (pintype "passive"))
      (node (ref "D12") (pin "1") (pinfunction "A_1") (pintype "passive"))
      (node (ref "D16") (pin "C") (pinfunction "C_C") (pintype "passive"))
      (node (ref "D2") (pin "C") (pinfunction "C_C") (pintype "passive"))
      (node (ref "D20") (pin "C") (pinfunction "C_C") (pintype "passive"))
      (node (ref "D3") (pin "C") (pinfunction "C_C") (pintype "passive"))
      (node (ref "D5") (pin "3") (pinfunction "A_3") (pintype "passive"))
      (node (ref "D6") (pin "A") (pinfunction "A_A") (pintype "passive"))
      (node (ref "D7") (pin "C") (pinfunction "C_C") (pintype "passive"))
      (node (ref "D9") (pin "1") (pinfunction "A_1") (pintype "passive"))
      (node (ref "IC2") (pin "18") (pinfunction "GND_18") (pintype "power_in"))
      (node (ref "IC2") (pin "35") (pinfunction "GND_35") (pintype "power_in"))
      (node (ref "IC2") (pin "42") (pinfunction "GND_42") (pintype "power_in"))
      (node (ref "IC2") (pin "5") (pinfunction "GND_5") (pintype "power_in"))
      (node (ref "IC2") (pin "TP") (pinfunction "GND_TP") (pintype "power_in"))
      (node (ref "IC4") (pin "1") (pinfunction "GND_1") (pintype "power_in"))
      (node (ref "IC5") (pin "10") (pinfunction "GND_10") (pintype "power_in"))
      (node (ref "IC6") (pin "1") (pinfunction "GND_1") (pintype "power_in"))
      (node (ref "J1") (pin "GND") (pinfunction "GND_GND") (pintype "power_in"))
      (node (ref "J1") (pin "GND2") (pinfunction "GND_GND2") (pintype "power_in"))
      (node (ref "J12") (pin "1") (pinfunction "1_1") (pintype "passive"))
      (node (ref "J13") (pin "1") (pinfunction "1_1") (pintype "passive"))
      (node (ref "J16") (pin "2-GND") (pinfunction "GND_2-GND") (pintype "power_in"))
      (node (ref "J2") (pin "1") (pinfunction "1_1") (pintype "passive"))
      (node (ref "J4") (pin "1") (pinfunction "1_1") (pintype "passive"))
      (node (ref "J5") (pin "1") (pinfunction "1_1") (pintype "passive"))
      (node (ref "R1") (pin "1") (pinfunction "1_1") (pintype "passive"))
      (node (ref "R19") (pin "2") (pinfunction "2_2") (pintype "passive"))
      (node (ref "R20") (pin "1") (pinfunction "1_1") (pintype "passive"))
      (node (ref "R32") (pin "2") (pinfunction "2_2") (pintype "passive"))
      (node (ref "R37") (pin "2") (pinfunction "2_2") (pintype "passive"))
      (node (ref "R46") (pin "2") (pinfunction "2_2") (pintype "passive"))
      (node (ref "R47") (pin "2") (pinfunction "2_2") (pintype "passive"))
      (node (ref "SD1") (pin "GND") (pinfunction "GND_GND") (pintype "bidirectional"))
      (node (ref "SD1") (pin "GND@1") (pinfunction "GND_GND@1") (pintype "bidirectional"))
      (node (ref "SD1") (pin "GND@2") (pinfunction "GND_GND@2") (pintype "bidirectional"))
      (node (ref "SD1") (pin "SW2") (pinfunction "SW2_SW2") (pintype "bidirectional"))
      (node (ref "SW1") (pin "3") (pinfunction "S1_3") (pintype "passive"))
      (node (ref "SW1") (pin "4") (pinfunction "S1_4") (pintype "passive"))
      (node (ref "SW2") (pin "1") (pinfunction "P1_1") (pintype "passive"))
      (node (ref "SW2") (pin "2") (pinfunction "P1_2") (pintype "passive"))
      (node (ref "T3") (pin "2") (pinfunction "S_2") (pintype "passive"))
      (node (ref "T5") (pin "1") (pinfunction "S_1") (pintype "passive"))
      (node (ref "T5") (pin "4") (pinfunction "S_4") (pintype "passive"))
      (node (ref "XBEE1") (pin "10") (pinfunction "GND_10") (pintype "power_in"))
    )
    (net (code "36") (name "I2C_SCL") (class "Default")
      (node (ref "J12") (pin "4") (pinfunction "4_4") (pintype "passive"))
      (node (ref "J13") (pin "4") (pinfunction "4_4") (pintype "passive"))
      (node (ref "R41") (pin "1") (pinfunction "1_1") (pintype "passive"))
      (node (ref "T6") (pin "6") (pinfunction "D_6") (pintype "passive"))
    )
    (net (code "37") (name "I2C_SDA") (class "Default")
      (node (ref "J12") (pin "3") (pinfunction "3_3") (pintype "passive"))
      (node (ref "J13") (pin "3") (pinfunction "3_3") (pintype "passive"))
      (node (ref "R42") (pin "1") (pinfunction "1_1") (pintype "passive"))
      (node (ref "T6") (pin "3") (pinfunction "D_3") (pintype "passive"))
    )
    (net (code "38") (name "I2C_VCC") (class "Default")
      (node (ref "C24") (pin "2") (pinfunction "2_2") (pintype "passive"))
      (node (ref "J12") (pin "2") (pinfunction "2_2") (pintype "passive"))
      (node (ref "J13") (pin "2") (pinfunction "2_2") (pintype "passive"))
      (node (ref "R41") (pin "2") (pinfunction "2_2") (pintype "passive"))
      (node (ref "R42") (pin "2") (pinfunction "2_2") (pintype "passive"))
      (node (ref "R43") (pin "2") (pinfunction "2_2") (pintype "passive"))
      (node (ref "T7") (pin "3") (pinfunction "D_3") (pintype "passive"))
    )
    (net (code "39") (name "IO1") (class "Default")
      (node (ref "J5") (pin "3") (pinfunction "3_3") (pintype "passive"))
      (node (ref "R31") (pin "2") (pinfunction "2_2") (pintype "passive"))
    )
    (net (code "40") (name "IO2") (class "Default")
      (node (ref "J5") (pin "4") (pinfunction "4_4") (pintype "passive"))
      (node (ref "R30") (pin "2") (pinfunction "2_2") (pintype "passive"))
    )
    (net (code "41") (name "Net-(D1-DI)") (class "Default")
      (node (ref "D1") (pin "4") (pinfunction "DI_4") (pintype "bidirectional"))
      (node (ref "R26") (pin "1") (pinfunction "1_1") (pintype "passive"))
    )
    (net (code "42") (name "Net-(D2-PadA)") (class "Default")
      (node (ref "D2") (pin "A") (pinfunction "A_A") (pintype "passive"))
      (node (ref "R3") (pin "2") (pinfunction "2_2") (pintype "passive"))
    )
    (net (code "43") (name "Net-(D3-PadA)") (class "Default")
      (node (ref "D3") (pin "A") (pinfunction "A_A") (pintype "passive"))
      (node (ref "R4") (pin "2") (pinfunction "2_2") (pintype "passive"))
    )
    (net (code "44") (name "Net-(D7-PadA)") (class "Default")
      (node (ref "D7") (pin "A") (pinfunction "A_A") (pintype "passive"))
      (node (ref "R22") (pin "1") (pinfunction "1_1") (pintype "passive"))
    )
    (net (code "45") (name "Net-(D16-PadA)") (class "Default")
      (node (ref "D16") (pin "A") (pinfunction "A_A") (pintype "passive"))
      (node (ref "R34") (pin "1") (pinfunction "1_1") (pintype "passive"))
    )
    (net (code "46") (name "Net-(D20-PadA)") (class "Default")
      (node (ref "D20") (pin "A") (pinfunction "A_A") (pintype "passive"))
      (node (ref "R43") (pin "1") (pinfunction "1_1") (pintype "passive"))
    )
    (net (code "47") (name "Net-(F1-Pad1)") (class "Default")
      (node (ref "F1") (pin "1") (pinfunction "1_1") (pintype "passive"))
      (node (ref "J1") (pin "VBUS") (pinfunction "VBUS_VBUS") (pintype "power_in"))
      (node (ref "J1") (pin "VBUS2") (pinfunction "VBUS_VBUS2") (pintype "power_in"))
    )
    (net (code "48") (name "Net-(IC2-(XIN32{slash}S1:0{slash}T2:0)PA00)") (class "Default")
      (node (ref "C14") (pin "1") (pinfunction "1_1") (pintype "passive"))
      (node (ref "IC2") (pin "1") (pinfunction "(XIN32/S1:0/T2:0)PA00_1") (pintype "bidirectional"))
      (node (ref "Q1") (pin "2") (pinfunction "2_2") (pintype "passive"))
    )
    (net (code "49") (name "Net-(IC2-(XOUT32{slash}S1:1{slash}T2:1)PA01)") (class "Default")
      (node (ref "C15") (pin "2") (pinfunction "2_2") (pintype "passive"))
      (node (ref "IC2") (pin "2") (pinfunction "(XOUT32/S1:1/T2:1)PA01_2") (pintype "bidirectional"))
      (node (ref "Q1") (pin "1") (pinfunction "1_1") (pintype "passive"))
    )
    (net (code "50") (name "Net-(IC2-VCCANA)") (class "Default")
      (node (ref "C10") (pin "2") (pinfunction "2_2") (pintype "passive"))
      (node (ref "C11") (pin "2") (pinfunction "2_2") (pintype "passive"))
      (node (ref "C8") (pin "2") (pinfunction "2_2") (pintype "passive"))
      (node (ref "IC2") (pin "6") (pinfunction "VCCANA_6") (pintype "power_in"))
      (node (ref "L1") (pin "2") (pinfunction "2_2") (pintype "passive"))
    )
    (net (code "51") (name "Net-(IC2-VCCCORE)") (class "Default")
      (node (ref "C13") (pin "2") (pinfunction "2_2") (pintype "passive"))
      (node (ref "IC2") (pin "43") (pinfunction "VCCCORE_43") (pintype "power_in"))
    )
    (net (code "52") (name "Net-(IC4-RST)") (class "Default")
      (node (ref "IC4") (pin "2") (pinfunction "RST_2") (pintype "output"))
      (node (ref "XBEE1") (pin "5") (pinfunction "~{RESET}_5") (pintype "bidirectional"))
    )
    (net (code "53") (name "Net-(IC5A-A1)") (class "Default")
      (node (ref "IC5") (pin "1") (pinfunction "G_1") (pintype "input"))
      (node (ref "IC5") (pin "2") (pinfunction "A1_2") (pintype "input"))
      (node (ref "R12") (pin "1") (pinfunction "1_1") (pintype "passive"))
      (node (ref "T1") (pin "6") (pinfunction "D_6") (pintype "passive"))
    )
    (net (code "54") (name "Net-(IC5B-A4)") (class "Default")
      (node (ref "IC5") (pin "17") (pinfunction "A4_17") (pintype "input"))
      (node (ref "IC5") (pin "19") (pinfunction "G_19") (pintype "input"))
      (node (ref "R13") (pin "1") (pinfunction "1_1") (pintype "passive"))
      (node (ref "T1") (pin "3") (pinfunction "D_3") (pintype "passive"))
    )
    (net (code "55") (name "Net-(J1-CC1)") (class "Default")
      (node (ref "J1") (pin "A5") (pinfunction "CC1_A5") (pintype "bidirectional"))
      (node (ref "R46") (pin "1") (pinfunction "1_1") (pintype "passive"))
    )
    (net (code "56") (name "Net-(J1-CC2)") (class "Default")
      (node (ref "J1") (pin "B5") (pinfunction "CC2_B5") (pintype "bidirectional"))
      (node (ref "R47") (pin "1") (pinfunction "1_1") (pintype "passive"))
    )
    (net (code "57") (name "Net-(J1-SHIELD-PadS@1)") (class "Default")
      (node (ref "J1") (pin "S@1") (pinfunction "SHIELD_S@1") (pintype "passive"))
      (node (ref "J1") (pin "S@2") (pinfunction "SHIELD_S@2") (pintype "passive"))
      (node (ref "J1") (pin "S@3") (pinfunction "SHIELD_S@3") (pintype "passive"))
      (node (ref "J1") (pin "S@4") (pinfunction "SHIELD_S@4") (pintype "passive"))
      (node (ref "J1") (pin "S@5") (pinfunction "SHIELD_S@5") (pintype "passive"))
      (node (ref "J1") (pin "S@6") (pinfunction "SHIELD_S@6") (pintype "passive"))
      (node (ref "J1") (pin "S@7") (pinfunction "SHIELD_S@7") (pintype "passive"))
      (node (ref "J1") (pin "S@8") (pinfunction "SHIELD_S@8") (pintype "passive"))
      (node (ref "J1") (pin "S@9") (pinfunction "SHIELD_S@9") (pintype "passive"))
      (node (ref "R1") (pin "2") (pinfunction "2_2") (pintype "passive"))
    )
    (net (code "58") (name "Net-(J4-Pad3)") (class "Default")
      (node (ref "J4") (pin "3") (pinfunction "3_3") (pintype "passive"))
      (node (ref "R25") (pin "2") (pinfunction "2_2") (pintype "passive"))
    )
    (net (code "59") (name "Net-(J4-Pad4)") (class "Default")
      (node (ref "J4") (pin "4") (pinfunction "4_4") (pintype "passive"))
      (node (ref "R24") (pin "2") (pinfunction "2_2") (pintype "passive"))
    )
    (net (code "60") (name "Net-(R2-Pad2)") (class "Default")
      (node (ref "R2") (pin "2") (pinfunction "2_2") (pintype "passive"))
      (node (ref "SW1") (pin "1") (pinfunction "P1_1") (pintype "passive"))
      (node (ref "SW1") (pin "2") (pinfunction "P1_2") (pintype "passive"))
    )
    (net (code "61") (name "Net-(R6-Pad2)") (class "Default")
      (node (ref "R6") (pin "2") (pinfunction "2_2") (pintype "passive"))
      (node (ref "SW2") (pin "3") (pinfunction "S1_3") (pintype "passive"))
      (node (ref "SW2") (pin "4") (pinfunction "S1_4") (pintype "passive"))
    )
    (net (code "62") (name "Net-(R17-Pad1)") (class "Default")
      (node (ref "R17") (pin "1") (pinfunction "1_1") (pintype "passive"))
      (node (ref "R9") (pin "1") (pinfunction "1_1") (pintype "passive"))
      (node (ref "SD1") (pin "SW1") (pinfunction "SW1_SW1") (pintype "bidirectional"))
    )
    (net (code "63") (name "Net-(T3-D)") (class "Default")
      (node (ref "J2") (pin "3") (pinfunction "3_3") (pintype "passive"))
      (node (ref "T3") (pin "3") (pinfunction "D_3") (pintype "passive"))
    )
    (net (code "64") (name "Net-(T3-G)") (class "Default")
      (node (ref "R11") (pin "1") (pinfunction "1_1") (pintype "passive"))
      (node (ref "R20") (pin "2") (pinfunction "2_2") (pintype "passive"))
      (node (ref "T3") (pin "1") (pinfunction "G_1") (pintype "passive"))
    )
    (net (code "65") (name "Net-(T4-G)") (class "Default")
      (node (ref "R33") (pin "2") (pinfunction "2_2") (pintype "passive"))
      (node (ref "T4") (pin "1") (pinfunction "G_1") (pintype "passive"))
      (node (ref "T5") (pin "3") (pinfunction "D_3") (pintype "passive"))
    )
    (net (code "66") (name "Net-(T5A-D)") (class "Default")
      (node (ref "R40") (pin "2") (pinfunction "2_2") (pintype "passive"))
      (node (ref "T5") (pin "6") (pinfunction "D_6") (pintype "passive"))
      (node (ref "T7") (pin "1") (pinfunction "G_1") (pintype "passive"))
    )
    (net (code "67") (name "Net-(XBEE1-DIN{slash}RX{slash}~{CFG})") (class "Default")
      (node (ref "R8") (pin "2") (pinfunction "2_2") (pintype "passive"))
      (node (ref "XBEE1") (pin "3") (pinfunction "DIN/RX/~{CFG}_3") (pintype "bidirectional"))
    )
    (net (code "68") (name "Net-(XBEE1-DIO7{slash}CTS)") (class "Default")
      (node (ref "R15") (pin "1") (pinfunction "1_1") (pintype "passive"))
      (node (ref "XBEE1") (pin "12") (pinfunction "DIO7/CTS_12") (pintype "bidirectional"))
    )
    (net (code "69") (name "Net-(XBEE1-DOUT{slash}TX)") (class "Default")
      (node (ref "R10") (pin "2") (pinfunction "2_2") (pintype "passive"))
      (node (ref "XBEE1") (pin "2") (pinfunction "DOUT/TX_2") (pintype "bidirectional"))
    )
    (net (code "70") (name "RST") (class "Default")
      (node (ref "C12") (pin "2") (pinfunction "2_2") (pintype "passive"))
      (node (ref "IC2") (pin "40") (pinfunction "~{RESET}_40") (pintype "input"))
      (node (ref "J16") (pin "3-RST") (pinfunction "RST_3-RST") (pintype "bidirectional"))
      (node (ref "R6") (pin "1") (pinfunction "1_1") (pintype "passive"))
      (node (ref "R7") (pin "2") (pinfunction "2_2") (pintype "passive"))
    )
    (net (code "71") (name "SWCLK") (class "Default")
      (node (ref "IC2") (pin "45") (pinfunction "(SWCLK/S1:2/T1:0)PA30_45") (pintype "bidirectional"))
      (node (ref "J16") (pin "4-SWDCLK") (pinfunction "SWCLK_4-SWDCLK") (pintype "bidirectional"))
      (node (ref "R5") (pin "2") (pinfunction "2_2") (pintype "passive"))
    )
    (net (code "72") (name "SWDIO") (class "Default")
      (node (ref "IC2") (pin "46") (pinfunction "(SWDIO/S1:3/T1:1)PA31_46") (pintype "bidirectional"))
      (node (ref "J16") (pin "5-SWDIO") (pinfunction "SWDIO_5-SWDIO") (pintype "bidirectional"))
    )
    (net (code "73") (name "UART_VCC") (class "Default")
      (node (ref "C23") (pin "2") (pinfunction "2_2") (pintype "passive"))
      (node (ref "J4") (pin "2") (pinfunction "2_2") (pintype "passive"))
      (node (ref "R34") (pin "2") (pinfunction "2_2") (pintype "passive"))
      (node (ref "T4") (pin "3") (pinfunction "D_3") (pintype "passive"))
    )
    (net (code "74") (name "USB_D_N") (class "Default")
      (node (ref "D5") (pin "1") (pinfunction "C1_1") (pintype "passive"))
      (node (ref "IC2") (pin "33") (pinfunction "(USBM/S3:2|5:2/T5:0|1:2)PA24_33") (pintype "bidirectional"))
      (node (ref "J1") (pin "A7") (pinfunction "D-_A7") (pintype "bidirectional"))
      (node (ref "J1") (pin "B7") (pinfunction "D-_B7") (pintype "bidirectional"))
    )
    (net (code "75") (name "USB_D_P") (class "Default")
      (node (ref "D5") (pin "2") (pinfunction "C2_2") (pintype "passive"))
      (node (ref "IC2") (pin "34") (pinfunction "(USBP/S3:3|5:3/T5:1|1:3)PA25_34") (pintype "bidirectional"))
      (node (ref "J1") (pin "A6") (pinfunction "D+_A6") (pintype "bidirectional"))
      (node (ref "J1") (pin "B6") (pinfunction "D+_B6") (pintype "bidirectional"))
    )
    (net (code "76") (name "XB1_CS") (class "Default")
      (node (ref "IC5") (pin "18") (pinfunction "Y1_18") (pintype "tri_state"))
      (node (ref "R14") (pin "1") (pinfunction "1_1") (pintype "passive"))
      (node (ref "XBEE1") (pin "17") (pinfunction "AD3/DIO3/SS_17") (pintype "bidirectional"))
    )
    (net (code "77") (name "XB1_MISO") (class "Default")
      (node (ref "IC5") (pin "8") (pinfunction "A4_8") (pintype "input"))
      (node (ref "XBEE1") (pin "4") (pinfunction "MISO/DIO12_4") (pintype "bidirectional"))
    )
    (net (code "78") (name "XB1_MOSI") (class "Default")
      (node (ref "IC5") (pin "16") (pinfunction "Y2_16") (pintype "tri_state"))
      (node (ref "XBEE1") (pin "11") (pinfunction "DIO4/MOSI_11") (pintype "bidirectional"))
    )
    (net (code "79") (name "XB1_SCK") (class "Default")
      (node (ref "IC5") (pin "14") (pinfunction "Y3_14") (pintype "tri_state"))
      (node (ref "XBEE1") (pin "18") (pinfunction "AD2/DIO2/SCK_18") (pintype "bidirectional"))
    )
    (net (code "80") (name "XB1_VCC") (class "Default")
      (node (ref "C16") (pin "2") (pinfunction "2_2") (pintype "passive"))
      (node (ref "C18") (pin "2") (pinfunction "2_2") (pintype "passive"))
      (node (ref "C20") (pin "2") (pinfunction "2_2") (pintype "passive"))
      (node (ref "IC4") (pin "3") (pinfunction "VCC_3") (pintype "power_in"))
      (node (ref "R14") (pin "2") (pinfunction "2_2") (pintype "passive"))
      (node (ref "R19") (pin "1") (pinfunction "1_1") (pintype "passive"))
      (node (ref "R22") (pin "2") (pinfunction "2_2") (pintype "passive"))
      (node (ref "T1") (pin "2") (pinfunction "G_2") (pintype "passive"))
      (node (ref "T2") (pin "3") (pinfunction "D_3") (pintype "passive"))
      (node (ref "XBEE1") (pin "1") (pinfunction "VCC_1") (pintype "power_in"))
    )
    (net (code "81") (name "XB2_CS") (class "Default")
      (node (ref "IC5") (pin "3") (pinfunction "Y4_3") (pintype "tri_state"))
      (node (ref "R16") (pin "1") (pinfunction "1_1") (pintype "passive"))
      (node (ref "SD1") (pin "CS") (pinfunction "~{CS}/DAT3_CS") (pintype "bidirectional"))
    )
    (net (code "82") (name "XB2_MISO") (class "Default")
      (node (ref "IC5") (pin "11") (pinfunction "A1_11") (pintype "input"))
      (node (ref "SD1") (pin "MISO") (pinfunction "MISO/DAT0_MISO") (pintype "bidirectional"))
    )
    (net (code "83") (name "XB2_MOSI") (class "Default")
      (node (ref "IC5") (pin "7") (pinfunction "Y2_7") (pintype "tri_state"))
      (node (ref "SD1") (pin "MOSI") (pinfunction "MOSI/CMD_MOSI") (pintype "bidirectional"))
    )
    (net (code "84") (name "XB2_SCK") (class "Default")
      (node (ref "IC5") (pin "5") (pinfunction "Y3_5") (pintype "tri_state"))
      (node (ref "SD1") (pin "SCK") (pinfunction "SCK_SCK") (pintype "bidirectional"))
    )
    (net (code "85") (name "unconnected-(D1-DO-Pad2)") (class "Default")
      (node (ref "D1") (pin "2") (pinfunction "DO_2") (pintype "bidirectional"))
    )
    (net (code "86") (name "unconnected-(J2-Pad4)") (class "Default")
      (node (ref "J2") (pin "4") (pinfunction "4_4") (pintype "passive"))
    )
    (net (code "87") (name "unconnected-(SD1-PadDAT1)") (class "Default")
      (node (ref "SD1") (pin "DAT1") (pinfunction "DAT1_DAT1") (pintype "bidirectional"))
    )
    (net (code "88") (name "unconnected-(SD1-PadDAT2)") (class "Default")
      (node (ref "SD1") (pin "DAT2") (pinfunction "DAT2_DAT2") (pintype "bidirectional"))
    )
    (net (code "89") (name "unconnected-(XBEE1-AD0{slash}DIO0{slash}SDA{slash}CB-Pad20)") (class "Default")
      (node (ref "XBEE1") (pin "20") (pinfunction "AD0/DIO0/SDA/CB_20") (pintype "bidirectional"))
    )
    (net (code "90") (name "unconnected-(XBEE1-AD1{slash}DIO1{slash}SCL{slash}ATTN-Pad19)") (class "Default")
      (node (ref "XBEE1") (pin "19") (pinfunction "AD1/DIO1/SCL/ATTN_19") (pintype "bidirectional"))
    )
    (net (code "91") (name "unconnected-(XBEE1-DIO5{slash}ASSC-Pad15)") (class "Default")
      (node (ref "XBEE1") (pin "15") (pinfunction "DIO5/ASSC_15") (pintype "bidirectional"))
    )
    (net (code "92") (name "unconnected-(XBEE1-DIO6{slash}RTS-Pad16)") (class "Default")
      (node (ref "XBEE1") (pin "16") (pinfunction "DIO6/RTS_16") (pintype "bidirectional"))
    )
    (net (code "93") (name "unconnected-(XBEE1-DIO9{slash}ON_~{SLEEP}-Pad13)") (class "Default")
      (node (ref "XBEE1") (pin "13") (pinfunction "DIO9/ON_~{SLEEP}_13") (pintype "bidirectional"))
    )
    (net (code "94") (name "unconnected-(XBEE1-DTR{slash}DIO8-Pad9)") (class "Default")
      (node (ref "XBEE1") (pin "9") (pinfunction "DTR/DIO8_9") (pintype "bidirectional"))
    )
    (net (code "95") (name "unconnected-(XBEE1-PWM1{slash}DIO11-Pad7)") (class "Default")
      (node (ref "XBEE1") (pin "7") (pinfunction "PWM1/DIO11_7") (pintype "bidirectional"))
    )
    (net (code "96") (name "unconnected-(XBEE1-RES-Pad8)") (class "Default")
      (node (ref "XBEE1") (pin "8") (pinfunction "RES_8") (pintype "bidirectional"))
    )
    (net (code "97") (name "unconnected-(XBEE1-RSSI{slash}PWM0{slash}DIO10-Pad6)") (class "Default")
      (node (ref "XBEE1") (pin "6") (pinfunction "RSSI/PWM0/DIO10_6") (pintype "bidirectional"))
    )
    (net (code "98") (name "unconnected-(XBEE1-VREF-Pad14)") (class "Default")
      (node (ref "XBEE1") (pin "14") (pinfunction "VREF_14") (pintype "bidirectional"))
    )
  )
)
